# lis2dh.net
KiCad netlist of a schematic drawn in Altium Designer
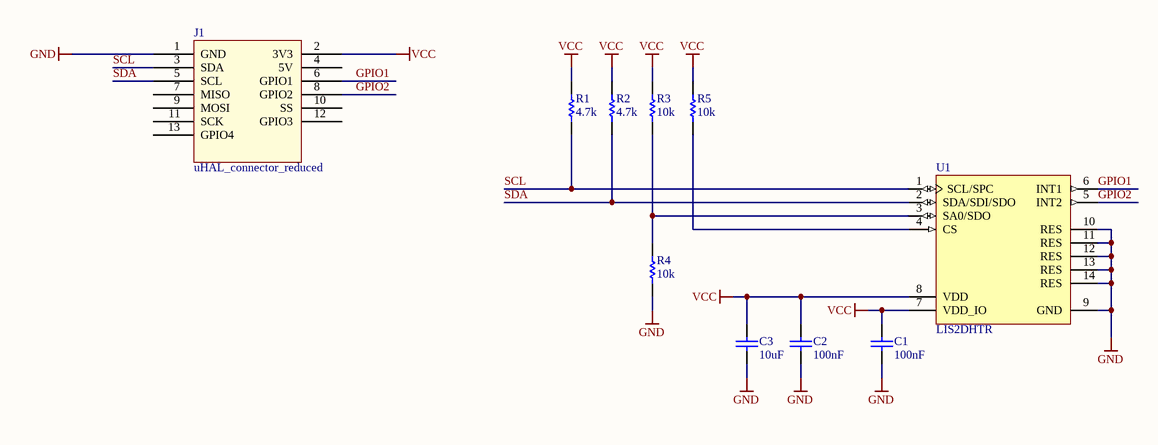
[diagram p0: lis2dh.SchDoc]

(export (version "E")
  (design (tool "Eeschema 10.0.6"))
  (components
    (comp (ref "C1")
      (value "Murata GCM188R71H104KA57D")
      (footprint "CAPC1608X90X35ML10T15")
      (description "CAP CER 0.1UF 50V 10% X7R 0603")
      (fields (field (name "CAPACITANCE") "100nF"))
      (libsource (lib "CommunityVault") (part "CMP-119667-3"))
    )
    (comp (ref "C2")
      (value "Murata GCM188R71H104KA57D")
      (footprint "CAPC1608X90X35ML10T15")
      (description "CAP CER 0.1UF 50V 10% X7R 0603")
      (fields (field (name "CAPACITANCE") "100nF"))
      (libsource (lib "CommunityVault") (part "CMP-119667-3"))
    )
    (comp (ref "C3")
      (value "Murata GCM188R71H104KA57D")
      (footprint "CAPC1608X90X35ML10T15")
      (description "CAP CER 0.1UF 50V 10% X7R 0603")
      (fields (field (name "CAPACITANCE") "10uF"))
      (libsource (lib "CommunityVault") (part "CMP-119667-3"))
    )
    (comp (ref "J1")
      (value "uHAL_connector_reduced")
      (footprint "PCB-45ncoppm4oopozvqifsq-1")
      (description "connector for uHAL with reduced pin number")
      (libsource (lib "CommunityVault") (part "CMP-2q23h2cwhjlfm8s6r7i8-1"))
    )
    (comp (ref "R1")
      (value "4.7k")
      (footprint "RESC1608X05N")
      (description "RCA Series 0603 0.1 W 0 O Jumper Surface Mount Thick Film Chip Resistor")
      (fields (field (name "MANUFACTURER PART NUMBER") "RCA06030000ZSEA"))
      (libsource (lib "CommunityVault") (part "SYM-31acf99032f6ee6b-1"))
    )
    (comp (ref "R2")
      (value "4.7k")
      (footprint "RESC1608X05N")
      (description "RCA Series 0603 0.1 W 0 O Jumper Surface Mount Thick Film Chip Resistor")
      (fields (field (name "MANUFACTURER PART NUMBER") "RCA06030000ZSEA"))
      (libsource (lib "CommunityVault") (part "SYM-31acf99032f6ee6b-1"))
    )
    (comp (ref "R3")
      (value "10k")
      (footprint "RESC1608X05N")
      (description "RCA Series 0603 0.1 W 0 O Jumper Surface Mount Thick Film Chip Resistor")
      (fields (field (name "MANUFACTURER PART NUMBER") "RCA06030000ZSEA"))
      (libsource (lib "CommunityVault") (part "SYM-31acf99032f6ee6b-1"))
    )
    (comp (ref "R4")
      (value "10k")
      (footprint "RESC1608X05N")
      (description "RCA Series 0603 0.1 W 0 O Jumper Surface Mount Thick Film Chip Resistor")
      (fields (field (name "MANUFACTURER PART NUMBER") "RCA06030000ZSEA"))
      (libsource (lib "CommunityVault") (part "SYM-31acf99032f6ee6b-1"))
    )
    (comp (ref "R5")
      (value "10k")
      (footprint "RESC1608X05N")
      (description "RCA Series 0603 0.1 W 0 O Jumper Surface Mount Thick Film Chip Resistor")
      (fields (field (name "MANUFACTURER PART NUMBER") "RCA06030000ZSEA"))
      (libsource (lib "CommunityVault") (part "SYM-31acf99032f6ee6b-1"))
    )
    (comp (ref "U1")
      (value "LIS2DHTR")
      (footprint "LGA-14_N")
      (libsource (lib "CommunityVault") (part "STM-LIS2DH-LGA-14"))
    )
  )
  (nets
    (net (code "1") (name "/GPIO1") (class "Default")
      (node (ref "J1") (pin "6") (pinfunction "GPIO1_6") (pintype "passive"))
      (node (ref "U1") (pin "6") (pinfunction "INT1_6") (pintype "output"))
    )
    (net (code "2") (name "/GPIO2") (class "Default")
      (node (ref "J1") (pin "8") (pinfunction "GPIO2_8") (pintype "passive"))
      (node (ref "U1") (pin "5") (pinfunction "INT2_5") (pintype "output"))
    )
    (net (code "3") (name "/SCL") (class "Default")
      (node (ref "J1") (pin "3") (pinfunction "SDA_3") (pintype "passive"))
      (node (ref "R1") (pin "1") (pinfunction "1_1") (pintype "passive"))
      (node (ref "U1") (pin "1") (pinfunction "SCL/SPC_1") (pintype "bidirectional"))
    )
    (net (code "4") (name "/SDA") (class "Default")
      (node (ref "J1") (pin "5") (pinfunction "SCL_5") (pintype "passive"))
      (node (ref "R2") (pin "1") (pinfunction "1_1") (pintype "passive"))
      (node (ref "U1") (pin "2") (pinfunction "SDA/SDI/SDO_2") (pintype "bidirectional"))
    )
    (net (code "5") (name "GND") (class "Default")
      (node (ref "C1") (pin "2") (pinfunction "2_2") (pintype "passive"))
      (node (ref "C2") (pin "2") (pinfunction "2_2") (pintype "passive"))
      (node (ref "C3") (pin "2") (pinfunction "2_2") (pintype "passive"))
      (node (ref "J1") (pin "1") (pinfunction "GND_1") (pintype "passive"))
      (node (ref "R4") (pin "1") (pinfunction "1_1") (pintype "passive"))
      (node (ref "U1") (pin "10") (pinfunction "RES_10") (pintype "power_in"))
      (node (ref "U1") (pin "11") (pinfunction "RES_11") (pintype "power_in"))
      (node (ref "U1") (pin "12") (pinfunction "RES_12") (pintype "power_in"))
      (node (ref "U1") (pin "13") (pinfunction "RES_13") (pintype "power_in"))
      (node (ref "U1") (pin "14") (pinfunction "RES_14") (pintype "power_in"))
      (node (ref "U1") (pin "9") (pinfunction "GND_9") (pintype "power_in"))
    )
    (net (code "6") (name "Net-(U1-CS)") (class "Default")
      (node (ref "R5") (pin "1") (pinfunction "1_1") (pintype "passive"))
      (node (ref "U1") (pin "4") (pinfunction "CS_4") (pintype "input"))
    )
    (net (code "7") (name "Net-(U1-SA0{slash}SDO)") (class "Default")
      (node (ref "R3") (pin "1") (pinfunction "1_1") (pintype "passive"))
      (node (ref "R4") (pin "2") (pinfunction "2_2") (pintype "passive"))
      (node (ref "U1") (pin "3") (pinfunction "SA0/SDO_3") (pintype "bidirectional"))
    )
    (net (code "8") (name "VCC") (class "Default")
      (node (ref "C1") (pin "1") (pinfunction "1_1") (pintype "passive"))
      (node (ref "C2") (pin "1") (pinfunction "1_1") (pintype "passive"))
      (node (ref "C3") (pin "1") (pinfunction "1_1") (pintype "passive"))
      (node (ref "J1") (pin "2") (pinfunction "3V3_2") (pintype "passive"))
      (node (ref "R1") (pin "2") (pinfunction "2_2") (pintype "passive"))
      (node (ref "R2") (pin "2") (pinfunction "2_2") (pintype "passive"))
      (node (ref "R3") (pin "2") (pinfunction "2_2") (pintype "passive"))
      (node (ref "R5") (pin "2") (pinfunction "2_2") (pintype "passive"))
      (node (ref "U1") (pin "7") (pinfunction "VDD_IO_7") (pintype "power_in"))
      (node (ref "U1") (pin "8") (pinfunction "VDD_8") (pintype "power_in"))
    )
    (net (code "9") (name "unconnected-(J1-5V-Pad4)") (class "Default")
      (node (ref "J1") (pin "4") (pinfunction "5V_4") (pintype "passive"))
    )
    (net (code "10") (name "unconnected-(J1-GPIO3-Pad12)") (class "Default")
      (node (ref "J1") (pin "12") (pinfunction "GPIO3_12") (pintype "passive"))
    )
    (net (code "11") (name "unconnected-(J1-GPIO4-Pad13)") (class "Default")
      (node (ref "J1") (pin "13") (pinfunction "GPIO4_13") (pintype "passive"))
    )
    (net (code "12") (name "unconnected-(J1-MISO-Pad7)") (class "Default")
      (node (ref "J1") (pin "7") (pinfunction "MISO_7") (pintype "passive"))
    )
    (net (code "13") (name "unconnected-(J1-MOSI-Pad9)") (class "Default")
      (node (ref "J1") (pin "9") (pinfunction "MOSI_9") (pintype "passive"))
    )
    (net (code "14") (name "unconnected-(J1-SCK-Pad11)") (class "Default")
      (node (ref "J1") (pin "11") (pinfunction "SCK_11") (pintype "passive"))
    )
    (net (code "15") (name "unconnected-(J1-SS-Pad10)") (class "Default")
      (node (ref "J1") (pin "10") (pinfunction "SS_10") (pintype "passive"))
    )
  )
)
